# Sheet1.net
KiCad netlist of a schematic drawn in Altium Designer
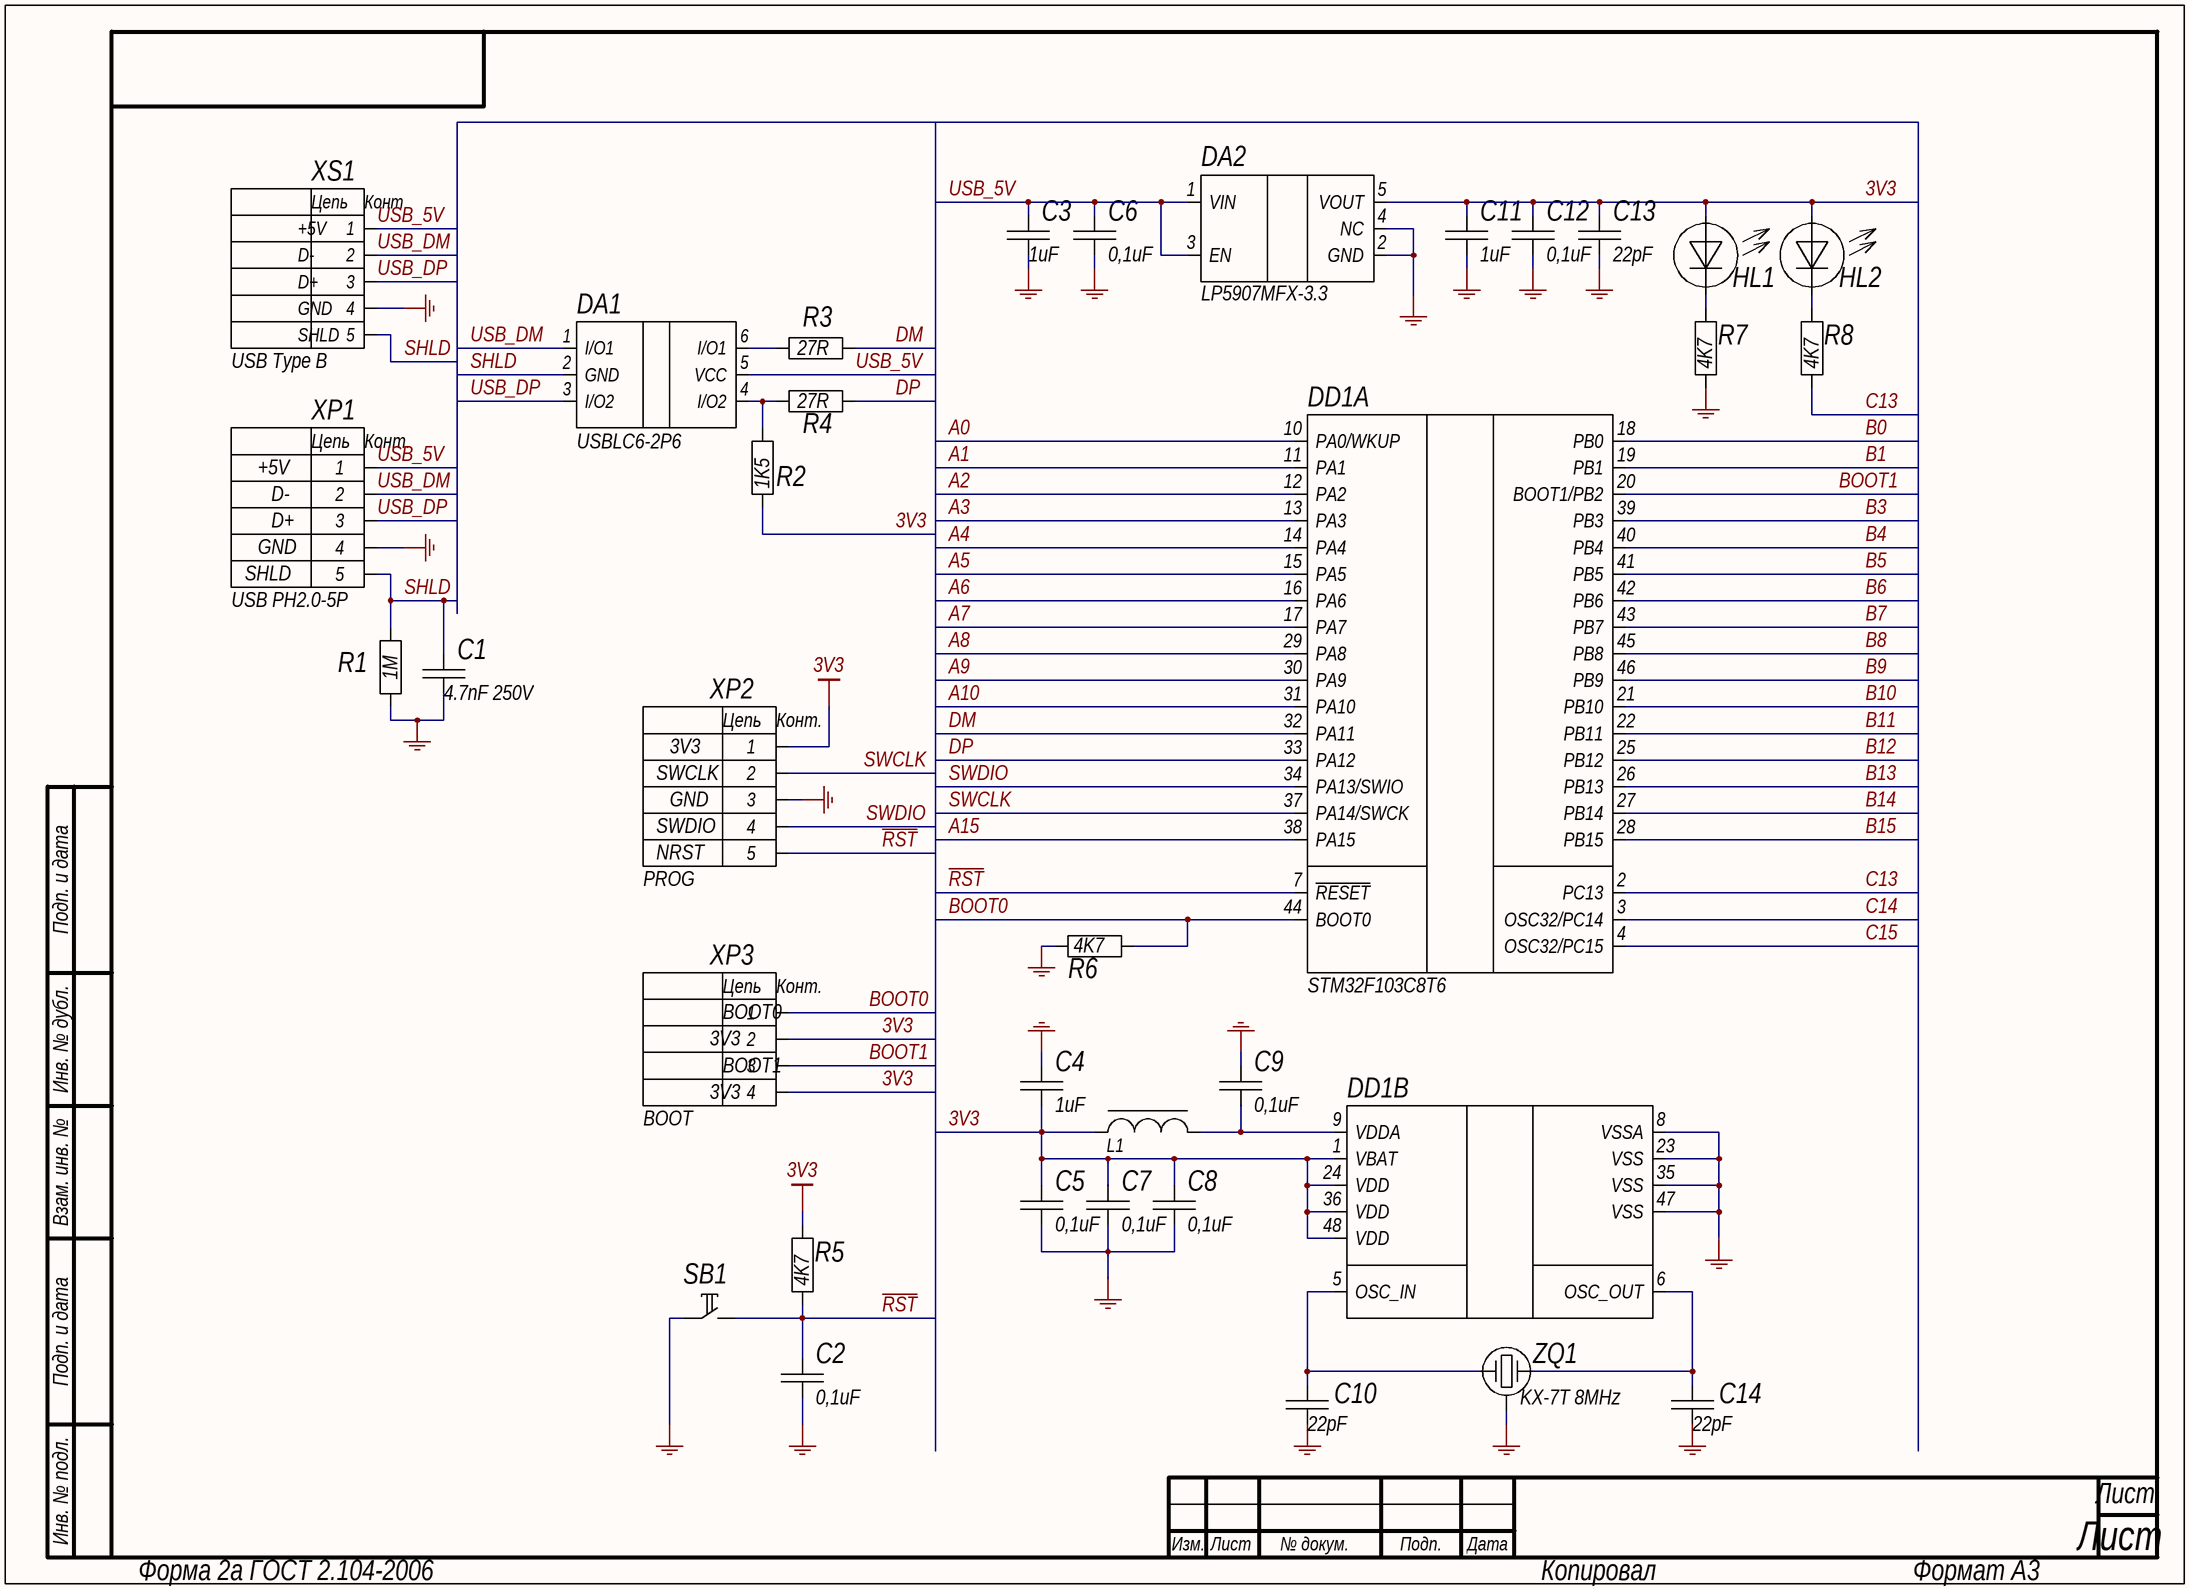
[diagram p0: Sheet1.SchDoc]

(export (version "E")
  (design (tool "Eeschema 10.0.6"))
  (components
    (comp (ref "C1")
      (value "4.7nF 250V")
      (footprint "CC0805_HD")
      (description "4700pF ± 5%, 250V, X7R, SMD 0805")
      (libsource (lib "Конденсаторы") (part "Конденсатор 0805 250 В 4,7 нФ ±10% X7R"))
    )
    (comp (ref "C2")
      (value "0,1uF")
      (footprint "CC0603_HD")
      (description "0.1uF ± 10%, 25V, X7R, SMD 0603")
      (fields (field (name "Comment") "100nF"))
      (libsource (lib "Конденсаторы") (part "Конденсатор 0603 50 В 0,1 мкФ ±10% X7R"))
    )
    (comp (ref "C3")
      (value "1uF")
      (footprint "CC0603_HD")
      (description "1uF ± 10%, 16V, X7R, SMD 0603")
      (libsource (lib "Конденсаторы") (part "Конденсатор 0603 16 В 1 мкФ ±10% X7R"))
    )
    (comp (ref "C4")
      (value "1uF")
      (footprint "CC0603_HD")
      (description "1uF ± 10%, 16V, X7R, SMD 0603")
      (libsource (lib "Конденсаторы") (part "Конденсатор 0603 16 В 1 мкФ ±10% X7R"))
    )
    (comp (ref "C5")
      (value "0,1uF")
      (footprint "CC0603_HD")
      (description "0.1uF ± 10%, 25V, X7R, SMD 0603")
      (fields (field (name "Comment") "100nF"))
      (libsource (lib "Конденсаторы") (part "Конденсатор 0603 50 В 0,1 мкФ ±10% X7R"))
    )
    (comp (ref "C6")
      (value "0,1uF")
      (footprint "CC0603_HD")
      (description "0.1uF ± 10%, 25V, X7R, SMD 0603")
      (fields (field (name "Comment") "100nF"))
      (libsource (lib "Конденсаторы") (part "Конденсатор 0603 50 В 0,1 мкФ ±10% X7R"))
    )
    (comp (ref "C7")
      (value "0,1uF")
      (footprint "CC0603_HD")
      (description "0.1uF ± 10%, 25V, X7R, SMD 0603")
      (fields (field (name "Comment") "100nF"))
      (libsource (lib "Конденсаторы") (part "Конденсатор 0603 50 В 0,1 мкФ ±10% X7R"))
    )
    (comp (ref "C8")
      (value "0,1uF")
      (footprint "CC0603_HD")
      (description "0.1uF ± 10%, 25V, X7R, SMD 0603")
      (fields (field (name "Comment") "100nF"))
      (libsource (lib "Конденсаторы") (part "Конденсатор 0603 50 В 0,1 мкФ ±10% X7R"))
    )
    (comp (ref "C9")
      (value "0,1uF")
      (footprint "CC0603_HD")
      (description "0.1uF ± 10%, 25V, X7R, SMD 0603")
      (fields (field (name "Comment") "100nF"))
      (libsource (lib "Конденсаторы") (part "Конденсатор 0603 50 В 0,1 мкФ ±10% X7R"))
    )
    (comp (ref "C10")
      (value "22pF")
      (footprint "CC0603_HD")
      (description "22pF ± 5%, 50V, NPO, SMD 0603")
      (libsource (lib "Конденсаторы") (part "Конденсатор 0603 50В 22 пФ ±5% NP0"))
    )
    (comp (ref "C11")
      (value "1uF")
      (footprint "CC0603_HD")
      (description "1uF ± 10%, 16V, X7R, SMD 0603")
      (libsource (lib "Конденсаторы") (part "Конденсатор 0603 16 В 1 мкФ ±10% X7R"))
    )
    (comp (ref "C12")
      (value "0,1uF")
      (footprint "CC0603_HD")
      (description "0.1uF ± 10%, 25V, X7R, SMD 0603")
      (fields (field (name "Comment") "100nF"))
      (libsource (lib "Конденсаторы") (part "Конденсатор 0603 50 В 0,1 мкФ ±10% X7R"))
    )
    (comp (ref "C13")
      (value "22pF")
      (footprint "CC0603_HD")
      (description "22pF ± 5%, 50V, NPO, SMD 0603")
      (libsource (lib "Конденсаторы") (part "Конденсатор 0603 50В 22 пФ ±5% NP0"))
    )
    (comp (ref "C14")
      (value "22pF")
      (footprint "CC0603_HD")
      (description "22pF ± 5%, 50V, NPO, SMD 0603")
      (libsource (lib "Конденсаторы") (part "Конденсатор 0603 50В 22 пФ ±5% NP0"))
    )
    (comp (ref "DA1")
      (value "USBLC6-2P6")
      (footprint "SOT666")
      (description "ESR protection IC, USBLC6-2P6, SOT666")
      (libsource (lib "Полупроводниковые приборы") (part "Диодная сборка USBLC6-2P6"))
    )
    (comp (ref "DA2")
      (value "LP5907MFX-3.3")
      (footprint "SOT23-5")
      (description "LDO voltage regulator, LP5907MFX-3.3, SOT23-5")
      (libsource (lib "Микросхемы") (part "Микросхема LP5907MFX-3.3"))
    )
    (comp (ref "DD1")
      (value "STM32F103C8T6")
      (footprint "LQFP48")
      (description "MCU, STM32F103C8T6, LQFP48")
      (libsource (lib "Микросхемы") (part "Микросхема STM32F103C8T6"))
    )
    (comp (ref "HL1")
      (value "KP-1608SRC")
      (footprint "LED0603R_HD")
      (description "KP-1608SRC, LED red, SMD 0603")
      (libsource (lib "Полупроводниковые приборы") (part "Светодиод KP-1608SRC"))
    )
    (comp (ref "HL2")
      (value "KP-1608SGC")
      (footprint "LED0603G_HD")
      (description "KP-1608SGC, LED green, SMD 0603")
      (libsource (lib "Полупроводниковые приборы") (part "Светодиод KP-1608SGC"))
    )
    (comp (ref "L1")
      (value "Ferrite bead, BLM18HG102SN1D")
      (footprint "RC0603_HD")
      (description "BLM18HG102SN1D, SMD 0603")
      (libsource (lib "Индуктивности, трансформаторы") (part "Индуктивность BLM18HG102SN1D"))
    )
    (comp (ref "R1")
      (value "1M")
      (footprint "RC0603_HD")
      (description "1M ± 1%, SMD 0603")
      (libsource (lib "Резисторы") (part "Резистор RC0603FR-071ML"))
    )
    (comp (ref "R2")
      (value "1K5")
      (footprint "RC0603_HD")
      (description "1K5 ± 1%, SMD 0603")
      (libsource (lib "Резисторы") (part "Резистор RC0603FR-071K5L"))
    )
    (comp (ref "R3")
      (value "27R")
      (footprint "RC0603_HD")
      (description "27R ± 1%, SMD 0603")
      (libsource (lib "Резисторы") (part "Резистор RC0603FR-0727RL"))
    )
    (comp (ref "R4")
      (value "27R")
      (footprint "RC0603_HD")
      (description "27R ± 1%, SMD 0603")
      (libsource (lib "Резисторы") (part "Резистор RC0603FR-0727RL"))
    )
    (comp (ref "R5")
      (value "4K7")
      (footprint "RC0603_HD")
      (description "4K7 ± 1%, SMD 0603")
      (libsource (lib "Резисторы") (part "Резистор RC0603FR-074K7L"))
    )
    (comp (ref "R6")
      (value "4K7")
      (footprint "RC0603_HD")
      (description "4K7 ± 1%, SMD 0603")
      (libsource (lib "Резисторы") (part "Резистор RC0603FR-074K7L"))
    )
    (comp (ref "R7")
      (value "4K7")
      (footprint "RC0603_HD")
      (description "4K7 ± 1%, SMD 0603")
      (libsource (lib "Резисторы") (part "Резистор RC0603FR-074K7L"))
    )
    (comp (ref "R8")
      (value "4K7")
      (footprint "RC0603_HD")
      (description "4K7 ± 1%, SMD 0603")
      (libsource (lib "Резисторы") (part "Резистор RC0603FR-074K7L"))
    )
    (comp (ref "SB1")
      (value "Tact Switch 3.5x6mm THT")
      (footprint "DTS-32")
      (description "DTS-32, 3.5x6mm, THT")
      (libsource (lib "Реле, кнопки, выключатели") (part "Кнопка DTS-32"))
    )
    (comp (ref "XP1")
      (value "USB PH2.0-5P")
      (footprint "PH2.0-5P")
      (description "PH2.0-5P")
      (libsource (lib "Соединители") (part "Вилка PH2.0-5P"))
    )
    (comp (ref "XP2")
      (value "PROG")
      (footprint "PLS-5")
      (description "PLS-5")
      (libsource (lib "Соединители") (part "Вилка DS1021-1x5"))
    )
    (comp (ref "XP3")
      (value "BOOT")
      (footprint "PLD-4")
      (description "PLD-4")
      (libsource (lib "Соединители") (part "Вилка DS1021-2x2"))
    )
    (comp (ref "XS1")
      (value "USB Type B")
      (footprint "DS1099-B")
      (description "DS1099, USB Type B Socket")
      (libsource (lib "Соединители") (part "Гнездо DS1099"))
    )
    (comp (ref "ZQ1")
      (value "KX-7T 8MHz")
      (footprint "CRYSTAL_3225")
      (description "Crystal Resonator, 8MHz, KX-7T")
      (libsource (lib "Кварцевые резонаторы") (part "Кварцевый резонатор KX-7T 8 МГц"))
    )
  )
  (nets
    (net (code "1") (name "/A0") (class "Default")
      (node (ref "DD1") (pin "10") (pinfunction "PA0/WKUP_10") (pintype "passive"))
    )
    (net (code "2") (name "/A1") (class "Default")
      (node (ref "DD1") (pin "11") (pinfunction "PA1_11") (pintype "passive"))
    )
    (net (code "3") (name "/A2") (class "Default")
      (node (ref "DD1") (pin "12") (pinfunction "PA2_12") (pintype "passive"))
    )
    (net (code "4") (name "/A3") (class "Default")
      (node (ref "DD1") (pin "13") (pinfunction "PA3_13") (pintype "passive"))
    )
    (net (code "5") (name "/A4") (class "Default")
      (node (ref "DD1") (pin "14") (pinfunction "PA4_14") (pintype "passive"))
    )
    (net (code "6") (name "/A5") (class "Default")
      (node (ref "DD1") (pin "15") (pinfunction "PA5_15") (pintype "passive"))
    )
    (net (code "7") (name "/A6") (class "Default")
      (node (ref "DD1") (pin "16") (pinfunction "PA6_16") (pintype "passive"))
    )
    (net (code "8") (name "/A7") (class "Default")
      (node (ref "DD1") (pin "17") (pinfunction "PA7_17") (pintype "passive"))
    )
    (net (code "9") (name "/A8") (class "Default")
      (node (ref "DD1") (pin "29") (pinfunction "PA8_29") (pintype "passive"))
    )
    (net (code "10") (name "/A9") (class "Default")
      (node (ref "DD1") (pin "30") (pinfunction "PA9_30") (pintype "passive"))
    )
    (net (code "11") (name "/A10") (class "Default")
      (node (ref "DD1") (pin "31") (pinfunction "PA10_31") (pintype "passive"))
    )
    (net (code "12") (name "/A15") (class "Default")
      (node (ref "DD1") (pin "38") (pinfunction "PA15_38") (pintype "passive"))
    )
    (net (code "13") (name "/B0") (class "Default")
      (node (ref "DD1") (pin "18") (pinfunction "PB0_18") (pintype "passive"))
    )
    (net (code "14") (name "/B1") (class "Default")
      (node (ref "DD1") (pin "19") (pinfunction "PB1_19") (pintype "passive"))
    )
    (net (code "15") (name "/B3") (class "Default")
      (node (ref "DD1") (pin "39") (pinfunction "PB3_39") (pintype "passive"))
    )
    (net (code "16") (name "/B4") (class "Default")
      (node (ref "DD1") (pin "40") (pinfunction "PB4_40") (pintype "passive"))
    )
    (net (code "17") (name "/B5") (class "Default")
      (node (ref "DD1") (pin "41") (pinfunction "PB5_41") (pintype "passive"))
    )
    (net (code "18") (name "/B6") (class "Default")
      (node (ref "DD1") (pin "42") (pinfunction "PB6_42") (pintype "passive"))
    )
    (net (code "19") (name "/B7") (class "Default")
      (node (ref "DD1") (pin "43") (pinfunction "PB7_43") (pintype "passive"))
    )
    (net (code "20") (name "/B8") (class "Default")
      (node (ref "DD1") (pin "45") (pinfunction "PB8_45") (pintype "passive"))
    )
    (net (code "21") (name "/B9") (class "Default")
      (node (ref "DD1") (pin "46") (pinfunction "PB9_46") (pintype "passive"))
    )
    (net (code "22") (name "/B10") (class "Default")
      (node (ref "DD1") (pin "21") (pinfunction "PB10_21") (pintype "passive"))
    )
    (net (code "23") (name "/B11") (class "Default")
      (node (ref "DD1") (pin "22") (pinfunction "PB11_22") (pintype "passive"))
    )
    (net (code "24") (name "/B12") (class "Default")
      (node (ref "DD1") (pin "25") (pinfunction "PB12_25") (pintype "passive"))
    )
    (net (code "25") (name "/B13") (class "Default")
      (node (ref "DD1") (pin "26") (pinfunction "PB13_26") (pintype "passive"))
    )
    (net (code "26") (name "/B14") (class "Default")
      (node (ref "DD1") (pin "27") (pinfunction "PB14_27") (pintype "passive"))
    )
    (net (code "27") (name "/B15") (class "Default")
      (node (ref "DD1") (pin "28") (pinfunction "PB15_28") (pintype "passive"))
    )
    (net (code "28") (name "/BOOT0") (class "Default")
      (node (ref "DD1") (pin "44") (pinfunction "BOOT0_44") (pintype "passive"))
      (node (ref "R6") (pin "1") (pinfunction "1_1") (pintype "passive"))
      (node (ref "XP3") (pin "1") (pinfunction "1_1") (pintype "passive"))
    )
    (net (code "29") (name "/BOOT1") (class "Default")
      (node (ref "DD1") (pin "20") (pinfunction "BOOT1/PB2_20") (pintype "passive"))
      (node (ref "XP3") (pin "3") (pinfunction "3_3") (pintype "passive"))
    )
    (net (code "30") (name "/C13") (class "Default")
      (node (ref "DD1") (pin "2") (pinfunction "PC13_2") (pintype "passive"))
      (node (ref "R8") (pin "1") (pinfunction "1_1") (pintype "passive"))
    )
    (net (code "31") (name "/C14") (class "Default")
      (node (ref "DD1") (pin "3") (pinfunction "OSC32/PC14_3") (pintype "passive"))
    )
    (net (code "32") (name "/C15") (class "Default")
      (node (ref "DD1") (pin "4") (pinfunction "OSC32/PC15_4") (pintype "passive"))
    )
    (net (code "33") (name "/DM") (class "Default")
      (node (ref "DD1") (pin "32") (pinfunction "PA11_32") (pintype "passive"))
      (node (ref "R3") (pin "2") (pinfunction "2_2") (pintype "passive"))
    )
    (net (code "34") (name "/DP") (class "Default")
      (node (ref "DD1") (pin "33") (pinfunction "PA12_33") (pintype "passive"))
      (node (ref "R4") (pin "2") (pinfunction "2_2") (pintype "passive"))
    )
    (net (code "35") (name "/SHLD") (class "Default")
      (node (ref "C1") (pin "2") (pinfunction "2_2") (pintype "passive"))
      (node (ref "DA1") (pin "2") (pinfunction "GND_2") (pintype "passive"))
      (node (ref "R1") (pin "2") (pinfunction "2_2") (pintype "passive"))
      (node (ref "XP1") (pin "5") (pinfunction "5_5") (pintype "passive"))
      (node (ref "XS1") (pin "5") (pinfunction "5_5") (pintype "passive"))
    )
    (net (code "36") (name "/SWCLK") (class "Default")
      (node (ref "DD1") (pin "37") (pinfunction "PA14/SWCK_37") (pintype "passive"))
      (node (ref "XP2") (pin "2") (pinfunction "2_2") (pintype "passive"))
    )
    (net (code "37") (name "/SWDIO") (class "Default")
      (node (ref "DD1") (pin "34") (pinfunction "PA13/SWIO_34") (pintype "passive"))
      (node (ref "XP2") (pin "4") (pinfunction "4_4") (pintype "passive"))
    )
    (net (code "38") (name "/USB_5V") (class "Default")
      (node (ref "C3") (pin "2") (pinfunction "2_2") (pintype "passive"))
      (node (ref "C6") (pin "2") (pinfunction "2_2") (pintype "passive"))
      (node (ref "DA1") (pin "5") (pinfunction "VCC_5") (pintype "passive"))
      (node (ref "DA2") (pin "1") (pinfunction "VIN_1") (pintype "passive"))
      (node (ref "DA2") (pin "3") (pinfunction "EN_3") (pintype "passive"))
      (node (ref "XP1") (pin "1") (pinfunction "1_1") (pintype "passive"))
      (node (ref "XS1") (pin "1") (pinfunction "1_1") (pintype "passive"))
    )
    (net (code "39") (name "/USB_DM") (class "Default")
      (node (ref "DA1") (pin "1") (pinfunction "I/O1_1") (pintype "passive"))
      (node (ref "XP1") (pin "2") (pinfunction "2_2") (pintype "passive"))
      (node (ref "XS1") (pin "2") (pinfunction "2_2") (pintype "passive"))
    )
    (net (code "40") (name "/USB_DP") (class "Default")
      (node (ref "DA1") (pin "3") (pinfunction "I/O2_3") (pintype "passive"))
      (node (ref "XP1") (pin "3") (pinfunction "3_3") (pintype "passive"))
      (node (ref "XS1") (pin "3") (pinfunction "3_3") (pintype "passive"))
    )
    (net (code "41") (name "/~{RST}") (class "Default")
      (node (ref "C2") (pin "2") (pinfunction "2_2") (pintype "passive"))
      (node (ref "DD1") (pin "7") (pinfunction "~{RESET}_7") (pintype "passive"))
      (node (ref "R5") (pin "2") (pinfunction "2_2") (pintype "passive"))
      (node (ref "SB1") (pin "2") (pinfunction "2_2") (pintype "passive"))
      (node (ref "XP2") (pin "5") (pinfunction "5_5") (pintype "passive"))
    )
    (net (code "42") (name "3V3") (class "Default")
      (node (ref "C11") (pin "2") (pinfunction "2_2") (pintype "passive"))
      (node (ref "C12") (pin "2") (pinfunction "2_2") (pintype "passive"))
      (node (ref "C13") (pin "2") (pinfunction "2_2") (pintype "passive"))
      (node (ref "C4") (pin "1") (pinfunction "1_1") (pintype "passive"))
      (node (ref "C5") (pin "2") (pinfunction "2_2") (pintype "passive"))
      (node (ref "C7") (pin "2") (pinfunction "2_2") (pintype "passive"))
      (node (ref "C8") (pin "2") (pinfunction "2_2") (pintype "passive"))
      (node (ref "DA2") (pin "5") (pinfunction "VOUT_5") (pintype "passive"))
      (node (ref "DD1") (pin "1") (pinfunction "VBAT_1") (pintype "passive"))
      (node (ref "DD1") (pin "24") (pinfunction "VDD_24") (pintype "passive"))
      (node (ref "DD1") (pin "36") (pinfunction "VDD_36") (pintype "passive"))
      (node (ref "DD1") (pin "48") (pinfunction "VDD_48") (pintype "passive"))
      (node (ref "HL1") (pin "A") (pinfunction "A_A") (pintype "passive"))
      (node (ref "HL2") (pin "A") (pinfunction "A_A") (pintype "passive"))
      (node (ref "L1") (pin "1") (pinfunction "1_1") (pintype "passive"))
      (node (ref "R2") (pin "2") (pinfunction "2_2") (pintype "passive"))
      (node (ref "R5") (pin "1") (pinfunction "1_1") (pintype "passive"))
      (node (ref "XP2") (pin "1") (pinfunction "1_1") (pintype "passive"))
      (node (ref "XP3") (pin "2") (pinfunction "2_2") (pintype "passive"))
      (node (ref "XP3") (pin "4") (pinfunction "4_4") (pintype "passive"))
    )
    (net (code "43") (name "GND") (class "Default")
      (node (ref "C1") (pin "1") (pinfunction "1_1") (pintype "passive"))
      (node (ref "C10") (pin "1") (pinfunction "1_1") (pintype "passive"))
      (node (ref "C11") (pin "1") (pinfunction "1_1") (pintype "passive"))
      (node (ref "C12") (pin "1") (pinfunction "1_1") (pintype "passive"))
      (node (ref "C13") (pin "1") (pinfunction "1_1") (pintype "passive"))
      (node (ref "C14") (pin "1") (pinfunction "1_1") (pintype "passive"))
      (node (ref "C2") (pin "1") (pinfunction "1_1") (pintype "passive"))
      (node (ref "C3") (pin "1") (pinfunction "1_1") (pintype "passive"))
      (node (ref "C4") (pin "2") (pinfunction "2_2") (pintype "passive"))
      (node (ref "C5") (pin "1") (pinfunction "1_1") (pintype "passive"))
      (node (ref "C6") (pin "1") (pinfunction "1_1") (pintype "passive"))
      (node (ref "C7") (pin "1") (pinfunction "1_1") (pintype "passive"))
      (node (ref "C8") (pin "1") (pinfunction "1_1") (pintype "passive"))
      (node (ref "C9") (pin "2") (pinfunction "2_2") (pintype "passive"))
      (node (ref "DA2") (pin "2") (pinfunction "GND_2") (pintype "passive"))
      (node (ref "DA2") (pin "4") (pinfunction "NC_4") (pintype "passive"))
      (node (ref "DD1") (pin "23") (pinfunction "VSS_23") (pintype "passive"))
      (node (ref "DD1") (pin "35") (pinfunction "VSS_35") (pintype "passive"))
      (node (ref "DD1") (pin "47") (pinfunction "VSS_47") (pintype "passive"))
      (node (ref "DD1") (pin "8") (pinfunction "VSSA_8") (pintype "passive"))
      (node (ref "R1") (pin "1") (pinfunction "1_1") (pintype "passive"))
      (node (ref "R6") (pin "2") (pinfunction "2_2") (pintype "passive"))
      (node (ref "R7") (pin "2") (pinfunction "2_2") (pintype "passive"))
      (node (ref "SB1") (pin "1") (pinfunction "1_1") (pintype "passive"))
      (node (ref "XP1") (pin "4") (pinfunction "4_4") (pintype "passive"))
      (node (ref "XP2") (pin "3") (pinfunction "3_3") (pintype "passive"))
      (node (ref "XS1") (pin "4") (pinfunction "4_4") (pintype "passive"))
      (node (ref "ZQ1") (pin "3") (pinfunction "GND_3") (pintype "power_in"))
    )
    (net (code "44") (name "Net-(DA1-I{slash}O1-Pad6)") (class "Default")
      (node (ref "DA1") (pin "6") (pinfunction "I/O1_6") (pintype "passive"))
      (node (ref "R3") (pin "1") (pinfunction "1_1") (pintype "passive"))
    )
    (net (code "45") (name "Net-(DA1-I{slash}O2-Pad4)") (class "Default")
      (node (ref "DA1") (pin "4") (pinfunction "I/O2_4") (pintype "passive"))
      (node (ref "R2") (pin "1") (pinfunction "1_1") (pintype "passive"))
      (node (ref "R4") (pin "1") (pinfunction "1_1") (pintype "passive"))
    )
    (net (code "46") (name "Net-(DD1B-OSC_IN)") (class "Default")
      (node (ref "C10") (pin "2") (pinfunction "2_2") (pintype "passive"))
      (node (ref "DD1") (pin "5") (pinfunction "OSC_IN_5") (pintype "passive"))
      (node (ref "ZQ1") (pin "1") (pinfunction "1_1") (pintype "passive"))
    )
    (net (code "47") (name "Net-(DD1B-OSC_OUT)") (class "Default")
      (node (ref "C14") (pin "2") (pinfunction "2_2") (pintype "passive"))
      (node (ref "DD1") (pin "6") (pinfunction "OSC_OUT_6") (pintype "passive"))
      (node (ref "ZQ1") (pin "2") (pinfunction "2_2") (pintype "passive"))
    )
    (net (code "48") (name "Net-(DD1B-VDDA)") (class "Default")
      (node (ref "C9") (pin "1") (pinfunction "1_1") (pintype "passive"))
      (node (ref "DD1") (pin "9") (pinfunction "VDDA_9") (pintype "passive"))
      (node (ref "L1") (pin "2") (pinfunction "2_2") (pintype "passive"))
    )
    (net (code "49") (name "Net-(HL1-PadC)") (class "Default")
      (node (ref "HL1") (pin "C") (pinfunction "C_C") (pintype "passive"))
      (node (ref "R7") (pin "1") (pinfunction "1_1") (pintype "passive"))
    )
    (net (code "50") (name "Net-(HL2-PadC)") (class "Default")
      (node (ref "HL2") (pin "C") (pinfunction "C_C") (pintype "passive"))
      (node (ref "R8") (pin "2") (pinfunction "2_2") (pintype "passive"))
    )
  )
)
